# Input_Devices.net
KiCad netlist of a schematic drawn in Altium Designer
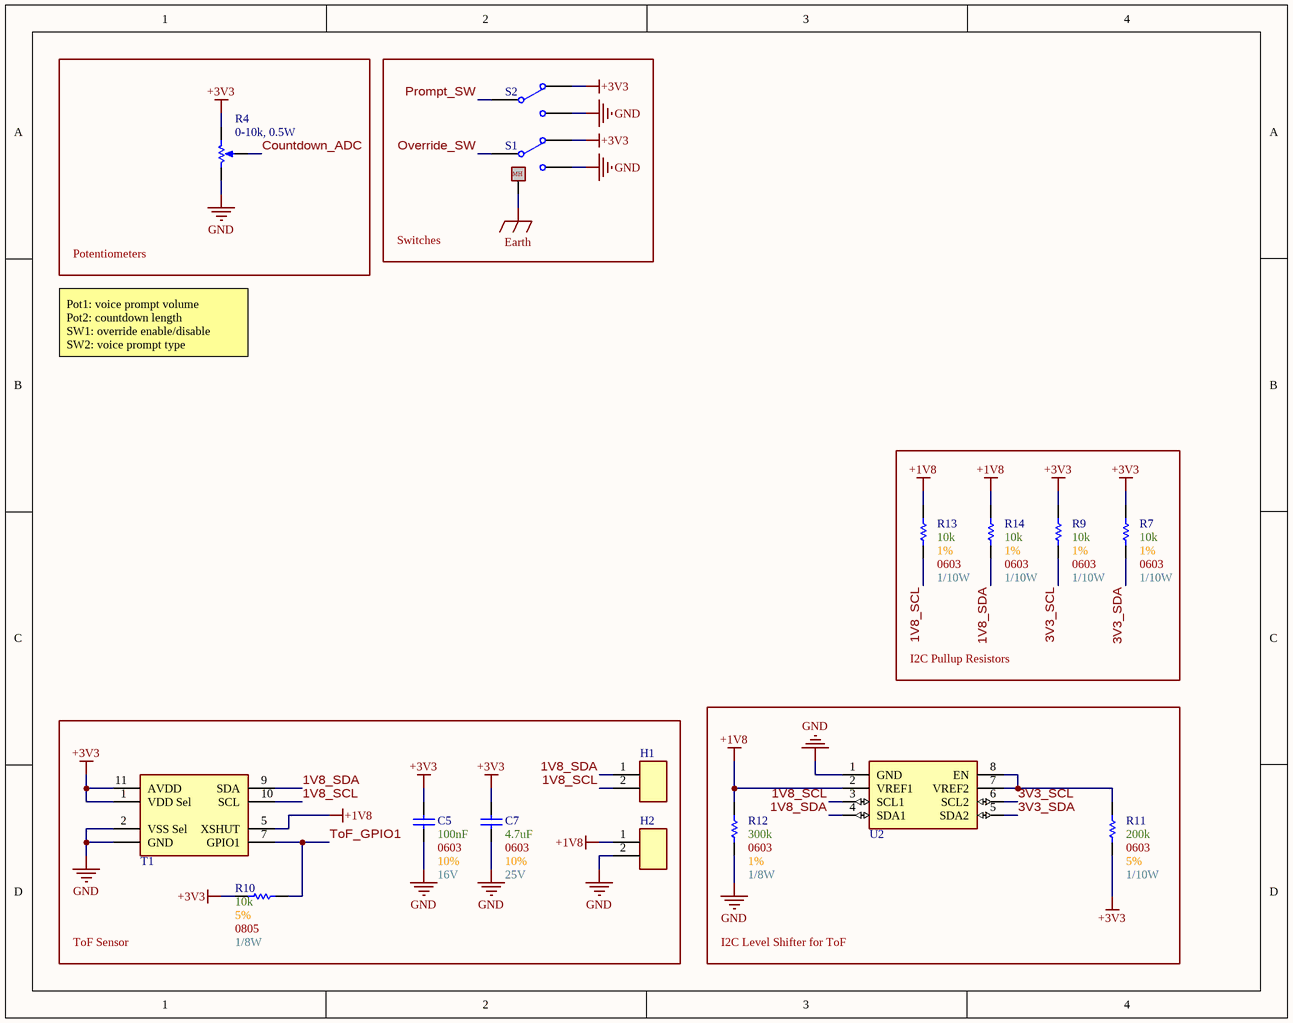
[diagram p0: Input Devices.SchDoc]

(export (version "E")
  (design (tool "Eeschema 10.0.6"))
  (components
    (comp (ref "C5")
      (value "[Cap] 0603 0.1uF 10% 16V")
      (footprint "[Cap] SMD 0603")
      (description "CC0603KRX7R7BB104")
      (fields
        (field (name "MAX VOLTAGE") "16V")
        (field (name "SIZE PACKAGE") "0603")
        (field (name "TOLERANCE") "10%")
        (field (name "CAPACITANCE") "100nF")
      )
      (libsource (lib "Capacitors") (part "[Cap] 0603 0.1uF 10% 16V"))
    )
    (comp (ref "C7")
      (value "[Cap] 0603 4.7uF 10% 25V")
      (footprint "[Cap] SMD 0603")
      (description "GRM188R61E475KE11D")
      (fields
        (field (name "MAX VOLTAGE") "25V")
        (field (name "SIZE PACKAGE") "0603")
        (field (name "TOLERANCE") "10%")
        (field (name "CAPACITANCE") "4.7uF")
      )
      (libsource (lib "Capacitors") (part "[Cap] 0603 4.7uF 10% 25V"))
    )
    (comp (ref "H1")
      (value "1x2 Header")
      (footprint "[Header] 1x2 Male")
      (description "2.54mm pitch")
      (libsource (lib "Connectors") (part "[Header] 1x2 Male"))
    )
    (comp (ref "H2")
      (value "1x2 Header")
      (footprint "[Header] 1x2 Male")
      (description "2.54mm pitch")
      (libsource (lib "Connectors") (part "[Header] 1x2 Male"))
    )
    (comp (ref "R4")
      (value "0-10k, 0.5W")
      (footprint "[Potentiometer] 10k 0.5W (2)")
      (description "3386T-1-103LF")
      (libsource (lib "Misc Components") (part "[Potentiometer] 10k 0.5W"))
    )
    (comp (ref "R7")
      (value "[10k] SMD 0603 1% 1/8W")
      (footprint "[Res] SMD 0603")
      (description "RMCF0603FT10K0")
      (fields
        (field (name "WATTAGE") "1/10W")
        (field (name "TOLERANCE") "1%")
        (field (name "RESISTANCE") "10k")
        (field (name "SIZE PACKAGE") "0603")
      )
      (libsource (lib "Resistors") (part "[10k] SMD 0603 1% 1/8W"))
    )
    (comp (ref "R9")
      (value "[10k] SMD 0603 1% 1/8W")
      (footprint "[Res] SMD 0603")
      (description "RMCF0603FT10K0")
      (fields
        (field (name "WATTAGE") "1/10W")
        (field (name "TOLERANCE") "1%")
        (field (name "RESISTANCE") "10k")
        (field (name "SIZE PACKAGE") "0603")
      )
      (libsource (lib "Resistors") (part "[10k] SMD 0603 1% 1/8W"))
    )
    (comp (ref "R10")
      (value "[10k] SMD 0603 1% 1/8W")
      (footprint "[Res] SMD 0603")
      (description "RC0805JR-0710KL")
      (fields
        (field (name "WATTAGE") "1/8W")
        (field (name "TOLERANCE") "5%")
        (field (name "RESISTANCE") "10k")
        (field (name "SIZE PACKAGE") "0805")
      )
      (libsource (lib "Resistors") (part "[10k] SMD 0603 1% 1/8W"))
    )
    (comp (ref "R11")
      (value "[200k] SMD 0603 1% 1/10W")
      (footprint "[Res] SMD 0603")
      (description "RC0603JR-07200KL")
      (fields
        (field (name "WATTAGE") "1/10W")
        (field (name "TOLERANCE") "5%")
        (field (name "RESISTANCE") "200k")
        (field (name "SIZE PACKAGE") "0603")
      )
      (libsource (lib "Resistors") (part "[200k] SMD 0603 1% 1/10W"))
    )
    (comp (ref "R12")
      (value "[300k] SMD 0603 1% 1/10W")
      (footprint "[Res] SMD 0603")
      (description "CRCW0603300KFKEA")
      (fields
        (field (name "WATTAGE") "1/8W")
        (field (name "TOLERANCE") "1%")
        (field (name "RESISTANCE") "300k")
        (field (name "SIZE PACKAGE") "0603")
      )
      (libsource (lib "Resistors") (part "[300k] SMD 0603 1% 1/10W"))
    )
    (comp (ref "R13")
      (value "[10k] SMD 0603 1% 1/8W")
      (footprint "[Res] SMD 0603")
      (description "RMCF0603FT10K0")
      (fields
        (field (name "WATTAGE") "1/10W")
        (field (name "TOLERANCE") "1%")
        (field (name "RESISTANCE") "10k")
        (field (name "SIZE PACKAGE") "0603")
      )
      (libsource (lib "Resistors") (part "[10k] SMD 0603 1% 1/8W"))
    )
    (comp (ref "R14")
      (value "[10k] SMD 0603 1% 1/8W")
      (footprint "[Res] SMD 0603")
      (description "RMCF0603FT10K0")
      (fields
        (field (name "WATTAGE") "1/10W")
        (field (name "TOLERANCE") "1%")
        (field (name "RESISTANCE") "10k")
        (field (name "SIZE PACKAGE") "0603")
      )
      (libsource (lib "Resistors") (part "[10k] SMD 0603 1% 1/8W"))
    )
    (comp (ref "S1")
      (value "[SPDT] Toggle")
      (footprint "[SPDT] Toggle")
      (description "ANT11TFHQE")
      (libsource (lib "Switches") (part "[SPDT] Toggle"))
    )
    (comp (ref "S2")
      (value "[SPDT] Slide Switch")
      (footprint "[SPDT] Slide Switch")
      (description "09.03290.01")
      (libsource (lib "Switches") (part "[SPDT] Slide Switch"))
    )
    (comp (ref "T1")
      (value "[ToF] VL53L1X")
      (footprint "[ToF] VL53L1X")
      (description "VL53L1CXV0FY/1")
      (libsource (lib "Devices") (part "[ToF] VL53L1X"))
    )
    (comp (ref "U2")
      (value "[Level Shifter] I2C Level Shifter")
      (footprint "[Level Shifter] I2C Level Shifter")
      (description "PCA9306DCTR")
      (libsource (lib "ICs") (part "[Level Shifter] I2C Level Shifter"))
    )
  )
  (nets
    (net (code "1") (name "+1V8") (class "Default")
      (node (ref "H2") (pin "1") (pintype "passive"))
      (node (ref "R12") (pin "2") (pinfunction "2_2") (pintype "passive"))
      (node (ref "R13") (pin "2") (pinfunction "2_2") (pintype "passive"))
      (node (ref "R14") (pin "2") (pinfunction "2_2") (pintype "passive"))
      (node (ref "T1") (pin "5") (pinfunction "XSHUT_5") (pintype "passive"))
      (node (ref "U2") (pin "2") (pinfunction "VREF1_2") (pintype "power_in"))
    )
    (net (code "2") (name "+3V3") (class "Default")
      (node (ref "C5") (pin "2") (pinfunction "2_2") (pintype "passive"))
      (node (ref "C7") (pin "2") (pinfunction "2_2") (pintype "passive"))
      (node (ref "R10") (pin "2") (pinfunction "2_2") (pintype "passive"))
      (node (ref "R11") (pin "1") (pinfunction "1_1") (pintype "passive"))
      (node (ref "R4") (pin "1") (pinfunction "TOP_1") (pintype "passive"))
      (node (ref "R7") (pin "2") (pinfunction "2_2") (pintype "passive"))
      (node (ref "R9") (pin "2") (pinfunction "2_2") (pintype "passive"))
      (node (ref "S1") (pin "3") (pinfunction "3_3") (pintype "passive"))
      (node (ref "S2") (pin "3") (pinfunction "3_3") (pintype "passive"))
      (node (ref "T1") (pin "1") (pinfunction "VDD_Sel_1") (pintype "power_in"))
      (node (ref "T1") (pin "11") (pinfunction "AVDD_11") (pintype "power_in"))
    )
    (net (code "3") (name "/1V8_SCL") (class "Default")
      (node (ref "H1") (pin "2") (pintype "passive"))
      (node (ref "R13") (pin "1") (pinfunction "1_1") (pintype "passive"))
      (node (ref "T1") (pin "10") (pinfunction "SCL_10") (pintype "passive"))
      (node (ref "U2") (pin "3") (pinfunction "SCL1_3") (pintype "bidirectional"))
    )
    (net (code "4") (name "/1V8_SDA") (class "Default")
      (node (ref "H1") (pin "1") (pintype "passive"))
      (node (ref "R14") (pin "1") (pinfunction "1_1") (pintype "passive"))
      (node (ref "T1") (pin "9") (pinfunction "SDA_9") (pintype "passive"))
      (node (ref "U2") (pin "4") (pinfunction "SDA1_4") (pintype "bidirectional"))
    )
    (net (code "5") (name "/3V3_SCL") (class "Default")
      (node (ref "R9") (pin "1") (pinfunction "1_1") (pintype "passive"))
      (node (ref "U2") (pin "6") (pinfunction "SCL2_6") (pintype "bidirectional"))
    )
    (net (code "6") (name "/3V3_SDA") (class "Default")
      (node (ref "R7") (pin "1") (pinfunction "1_1") (pintype "passive"))
      (node (ref "U2") (pin "5") (pinfunction "SDA2_5") (pintype "bidirectional"))
    )
    (net (code "7") (name "/Countdown_ADC") (class "Default")
      (node (ref "R4") (pin "2") (pinfunction "TAP_2") (pintype "passive"))
    )
    (net (code "8") (name "/Override_SW") (class "Default")
      (node (ref "S1") (pin "2") (pinfunction "2_2") (pintype "passive"))
    )
    (net (code "9") (name "/Prompt_SW") (class "Default")
      (node (ref "S2") (pin "2") (pinfunction "2_2") (pintype "passive"))
    )
    (net (code "10") (name "/ToF_GPIO1") (class "Default")
      (node (ref "R10") (pin "1") (pinfunction "1_1") (pintype "passive"))
      (node (ref "T1") (pin "7") (pinfunction "GPIO1_7") (pintype "passive"))
    )
    (net (code "11") (name "Earth") (class "Default")
      (node (ref "S1") (pin "X") (pinfunction "Mount_Hole_X") (pintype "passive"))
    )
    (net (code "12") (name "GND") (class "Default")
      (node (ref "C5") (pin "1") (pinfunction "1_1") (pintype "passive"))
      (node (ref "C7") (pin "1") (pinfunction "1_1") (pintype "passive"))
      (node (ref "H2") (pin "2") (pintype "passive"))
      (node (ref "R12") (pin "1") (pinfunction "1_1") (pintype "passive"))
      (node (ref "R4") (pin "3") (pinfunction "BOT_3") (pintype "passive"))
      (node (ref "S1") (pin "1") (pinfunction "1_1") (pintype "passive"))
      (node (ref "S2") (pin "1") (pinfunction "1_1") (pintype "passive"))
      (node (ref "T1") (pin "2") (pinfunction "VSS_Sel_2") (pintype "power_in"))
      (node (ref "T1") (pin "GND") (pinfunction "GND_GND") (pintype "power_in"))
      (node (ref "U2") (pin "1") (pinfunction "GND_1") (pintype "power_in"))
    )
    (net (code "13") (name "Net-(U2-EN)") (class "Default")
      (node (ref "R11") (pin "2") (pinfunction "2_2") (pintype "passive"))
      (node (ref "U2") (pin "7") (pinfunction "VREF2_7") (pintype "power_in"))
      (node (ref "U2") (pin "8") (pinfunction "EN_8") (pintype "passive"))
    )
  )
)
